# main.net
KiCad netlist of a schematic drawn in EAGLE
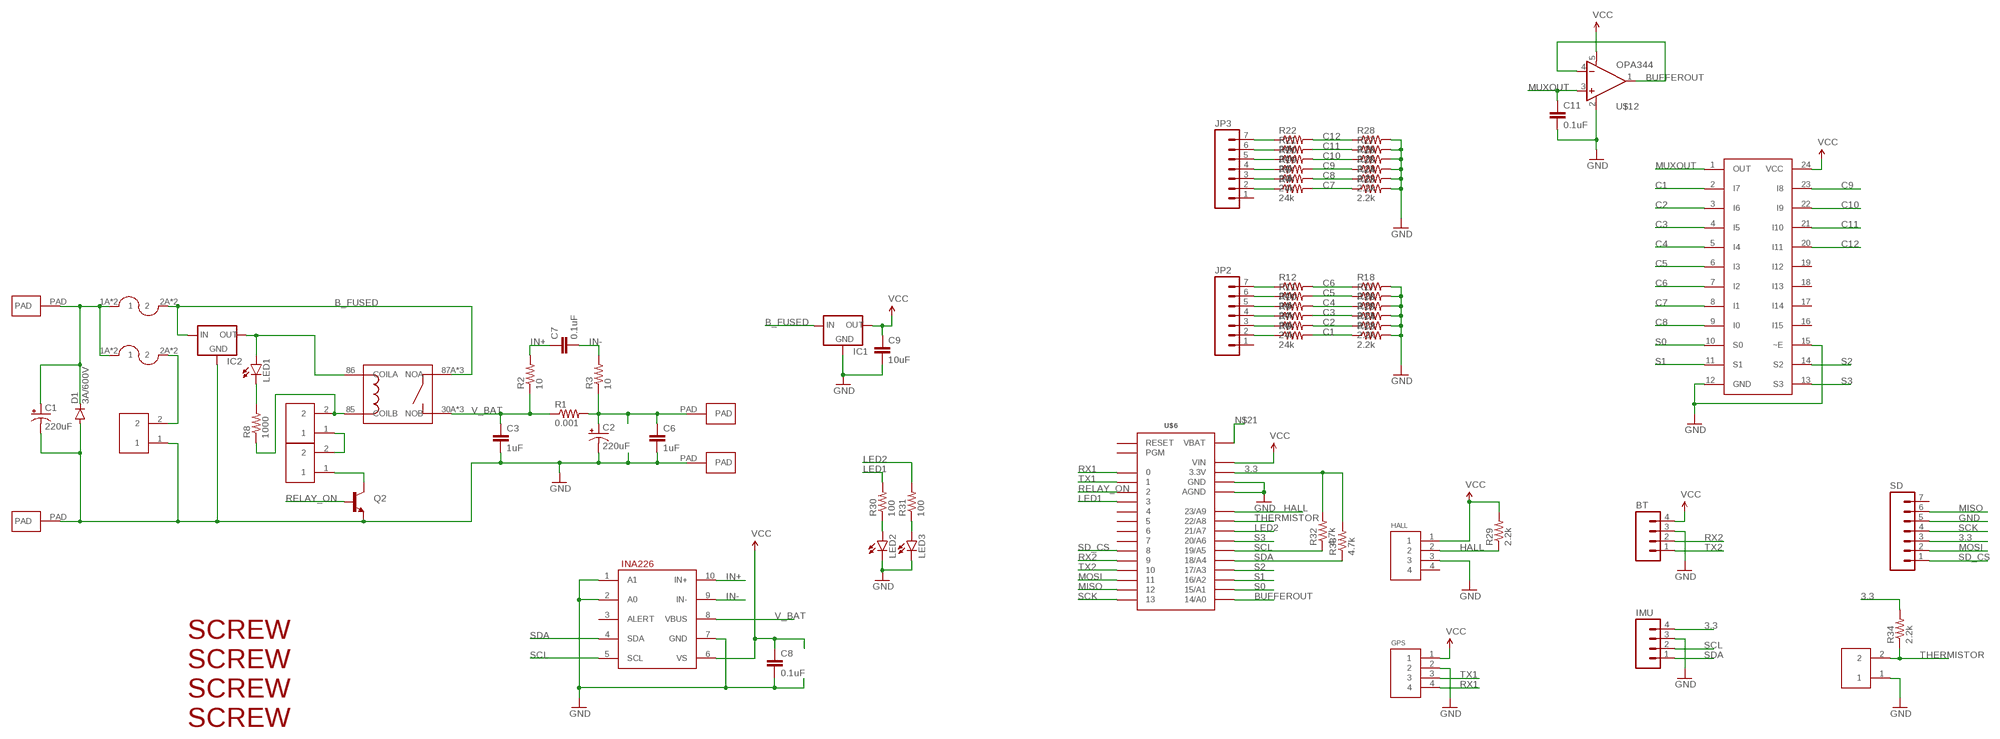
[diagram p0: schematic, sheet 1]

(export (version "E")
  (design (tool "Eeschema 10.0.6"))
  (components
    (comp (ref "BT")
      (value "M04PTH")
      (footprint "eagle-import:1X04")
      (libsource (lib "eagle-import") (part "M04PTH"))
    )
    (comp (ref "C1")
      (value "220uF")
      (footprint "eagle-import:CPOL-RADIAL-1000UF-25V")
      (libsource (lib "eagle-import") (part "CAP_POLPTH4"))
    )
    (comp (ref "C2")
      (value "220uF")
      (footprint "eagle-import:CPOL-RADIAL-1000UF-25V")
      (libsource (lib "eagle-import") (part "CAP_POLPTH4"))
    )
    (comp (ref "C3")
      (value "1uF")
      (footprint "eagle-import:1206")
      (libsource (lib "eagle-import") (part "CAP1206"))
    )
    (comp (ref "C6")
      (value "1uF")
      (footprint "eagle-import:1206")
      (libsource (lib "eagle-import") (part "CAP1206"))
    )
    (comp (ref "C7")
      (value "0.1uF")
      (footprint "eagle-import:0603-CAP")
      (libsource (lib "eagle-import") (part "SparkFun-Passives_CAP0603-CAP"))
    )
    (comp (ref "C8")
      (value "0.1uF")
      (footprint "eagle-import:0603-CAP")
      (libsource (lib "eagle-import") (part "SparkFun-Passives_CAP0603-CAP"))
    )
    (comp (ref "C9")
      (value "10uF")
      (footprint "eagle-import:0805")
      (libsource (lib "eagle-import") (part "SparkFun-Passives_CAP0805"))
    )
    (comp (ref "C11")
      (value "0.1uF")
      (footprint "eagle-import:0603-CAP")
      (libsource (lib "eagle-import") (part "SparkFun-Passives_CAP0603-CAP"))
    )
    (comp (ref "D1")
      (value "3A/600V")
      (footprint "eagle-import:SMC")
      (libsource (lib "eagle-import") (part "DIODEES3J"))
    )
    (comp (ref "GPS")
      (value "GPS")
      (footprint "eagle-import:4PINVALULOK")
      (libsource (lib "eagle-import") (part "HEADER4VALULOK"))
    )
    (comp (ref "HALL")
      (value "HEADER4VALULOK")
      (footprint "eagle-import:4PINVALULOK")
      (libsource (lib "eagle-import") (part "HEADER4VALULOK"))
    )
    (comp (ref "IC1")
      (value "V_REG_78XXSINK")
      (footprint "eagle-import:TO220-IGO")
      (libsource (lib "eagle-import") (part "V_REG_78XXSINK"))
    )
    (comp (ref "IC2")
      (value "V_REG_78XXSINK")
      (footprint "eagle-import:TO220-IGO")
      (libsource (lib "eagle-import") (part "V_REG_78XXSINK"))
    )
    (comp (ref "IMU")
      (value "M04PTH")
      (footprint "eagle-import:1X04")
      (libsource (lib "eagle-import") (part "M04PTH"))
    )
    (comp (ref "JP2")
      (value "M07")
      (footprint "eagle-import:1X07")
      (libsource (lib "eagle-import") (part "M07"))
    )
    (comp (ref "JP3")
      (value "M07")
      (footprint "eagle-import:1X07")
      (libsource (lib "eagle-import") (part "M07"))
    )
    (comp (ref "LED1")
      (value "LED1206")
      (footprint "eagle-import:LED-1206")
      (libsource (lib "eagle-import") (part "LED1206"))
    )
    (comp (ref "LED2")
      (value "LED1206")
      (footprint "eagle-import:LED-1206")
      (libsource (lib "eagle-import") (part "LED1206"))
    )
    (comp (ref "LED3")
      (value "LED1206")
      (footprint "eagle-import:LED-1206")
      (libsource (lib "eagle-import") (part "LED1206"))
    )
    (comp (ref "Q2")
      (value "TRANSISTOR_NPNSMD2")
      (footprint "eagle-import:SOT223")
      (libsource (lib "eagle-import") (part "TRANSISTOR_NPNSMD2"))
    )
    (comp (ref "R1")
      (value "0.001")
      (footprint "eagle-import:R2512")
      (libsource (lib "eagle-import") (part "SparkFun-Resistors_RESISTOR2512"))
    )
    (comp (ref "R2")
      (value "10")
      (footprint "eagle-import:0603-RES")
      (libsource (lib "eagle-import") (part "RESISTOR0603-RES"))
    )
    (comp (ref "R3")
      (value "10")
      (footprint "eagle-import:0603-RES")
      (libsource (lib "eagle-import") (part "RESISTOR0603-RES"))
    )
    (comp (ref "R4")
      (value "24k")
      (footprint "eagle-import:0603-RES")
      (libsource (lib "eagle-import") (part "RESISTOR0603-RES"))
    )
    (comp (ref "R5")
      (value "24k")
      (footprint "eagle-import:0603-RES")
      (libsource (lib "eagle-import") (part "RESISTOR0603-RES"))
    )
    (comp (ref "R6")
      (value "24k")
      (footprint "eagle-import:0603-RES")
      (libsource (lib "eagle-import") (part "RESISTOR0603-RES"))
    )
    (comp (ref "R7")
      (value "24k")
      (footprint "eagle-import:0603-RES")
      (libsource (lib "eagle-import") (part "RESISTOR0603-RES"))
    )
    (comp (ref "R8")
      (value "1000")
      (footprint "eagle-import:0603-RES")
      (libsource (lib "eagle-import") (part "RESISTOR0603-RES"))
    )
    (comp (ref "R9")
      (value "24k")
      (footprint "eagle-import:0603-RES")
      (libsource (lib "eagle-import") (part "RESISTOR0603-RES"))
    )
    (comp (ref "R10")
      (value "24k")
      (footprint "eagle-import:0603-RES")
      (libsource (lib "eagle-import") (part "RESISTOR0603-RES"))
    )
    (comp (ref "R11")
      (value "24k")
      (footprint "eagle-import:0603-RES")
      (libsource (lib "eagle-import") (part "RESISTOR0603-RES"))
    )
    (comp (ref "R12")
      (value "24k")
      (footprint "eagle-import:0603-RES")
      (libsource (lib "eagle-import") (part "RESISTOR0603-RES"))
    )
    (comp (ref "R13")
      (value "2.2k")
      (footprint "eagle-import:0603-RES")
      (libsource (lib "eagle-import") (part "RESISTOR0603-RES"))
    )
    (comp (ref "R14")
      (value "2.2k")
      (footprint "eagle-import:0603-RES")
      (libsource (lib "eagle-import") (part "RESISTOR0603-RES"))
    )
    (comp (ref "R15")
      (value "2.2k")
      (footprint "eagle-import:0603-RES")
      (libsource (lib "eagle-import") (part "RESISTOR0603-RES"))
    )
    (comp (ref "R16")
      (value "2.2k")
      (footprint "eagle-import:0603-RES")
      (libsource (lib "eagle-import") (part "RESISTOR0603-RES"))
    )
    (comp (ref "R17")
      (value "2.2k")
      (footprint "eagle-import:0603-RES")
      (libsource (lib "eagle-import") (part "RESISTOR0603-RES"))
    )
    (comp (ref "R18")
      (value "2.2k")
      (footprint "eagle-import:0603-RES")
      (libsource (lib "eagle-import") (part "RESISTOR0603-RES"))
    )
    (comp (ref "R19")
      (value "24k")
      (footprint "eagle-import:0603-RES")
      (libsource (lib "eagle-import") (part "RESISTOR0603-RES"))
    )
    (comp (ref "R20")
      (value "24k")
      (footprint "eagle-import:0603-RES")
      (libsource (lib "eagle-import") (part "RESISTOR0603-RES"))
    )
    (comp (ref "R21")
      (value "24k")
      (footprint "eagle-import:0603-RES")
      (libsource (lib "eagle-import") (part "RESISTOR0603-RES"))
    )
    (comp (ref "R22")
      (value "24k")
      (footprint "eagle-import:0603-RES")
      (libsource (lib "eagle-import") (part "RESISTOR0603-RES"))
    )
    (comp (ref "R23")
      (value "2.2k")
      (footprint "eagle-import:0603-RES")
      (libsource (lib "eagle-import") (part "RESISTOR0603-RES"))
    )
    (comp (ref "R24")
      (value "2.2k")
      (footprint "eagle-import:0603-RES")
      (libsource (lib "eagle-import") (part "RESISTOR0603-RES"))
    )
    (comp (ref "R25")
      (value "2.2k")
      (footprint "eagle-import:0603-RES")
      (libsource (lib "eagle-import") (part "RESISTOR0603-RES"))
    )
    (comp (ref "R26")
      (value "2.2k")
      (footprint "eagle-import:0603-RES")
      (libsource (lib "eagle-import") (part "RESISTOR0603-RES"))
    )
    (comp (ref "R27")
      (value "2.2k")
      (footprint "eagle-import:0603-RES")
      (libsource (lib "eagle-import") (part "RESISTOR0603-RES"))
    )
    (comp (ref "R28")
      (value "2.2k")
      (footprint "eagle-import:0603-RES")
      (libsource (lib "eagle-import") (part "RESISTOR0603-RES"))
    )
    (comp (ref "R29")
      (value "2.2k")
      (footprint "eagle-import:0603-RES")
      (libsource (lib "eagle-import") (part "RESISTOR0603-RES"))
    )
    (comp (ref "R30")
      (value "100")
      (footprint "eagle-import:0603-RES")
      (libsource (lib "eagle-import") (part "RESISTOR0603-RES"))
    )
    (comp (ref "R31")
      (value "100")
      (footprint "eagle-import:0603-RES")
      (libsource (lib "eagle-import") (part "RESISTOR0603-RES"))
    )
    (comp (ref "R32")
      (value "4.7k")
      (footprint "eagle-import:0603-RES")
      (libsource (lib "eagle-import") (part "RESISTOR0603-RES"))
    )
    (comp (ref "R33")
      (value "4.7k")
      (footprint "eagle-import:0603-RES")
      (libsource (lib "eagle-import") (part "RESISTOR0603-RES"))
    )
    (comp (ref "R34")
      (value "2.2k")
      (footprint "eagle-import:0603-RES")
      (libsource (lib "eagle-import") (part "RESISTOR0603-RES"))
    )
    (comp (ref "SD")
      (value "M07")
      (footprint "eagle-import:1X07")
      (libsource (lib "eagle-import") (part "M07"))
    )
    (comp (ref "U$1")
      (value "INA226")
      (footprint "eagle-import:PSOP-10")
      (libsource (lib "eagle-import") (part "INA226"))
    )
    (comp (ref "U$2")
      (value "PAD")
      (footprint "eagle-import:PAD")
      (libsource (lib "eagle-import") (part "PAD"))
    )
    (comp (ref "U$3")
      (value "PAD")
      (footprint "eagle-import:PAD")
      (libsource (lib "eagle-import") (part "PAD"))
    )
    (comp (ref "U$4")
      (value "PAD")
      (footprint "eagle-import:PAD")
      (libsource (lib "eagle-import") (part "PAD"))
    )
    (comp (ref "U$5")
      (value "PAD")
      (footprint "eagle-import:PAD")
      (libsource (lib "eagle-import") (part "PAD"))
    )
    (comp (ref "U$6")
      (value "TEENSY_3.0_BASIC")
      (footprint "eagle-import:TEENSY_3.0_BASIC")
      (libsource (lib "eagle-import") (part "TEENSY_3.0_BASIC"))
    )
    (comp (ref "U$7")
      (value "RELAY")
      (footprint "eagle-import:PANASONIC_HP_RELAY")
      (libsource (lib "eagle-import") (part "RELAY"))
    )
    (comp (ref "U$8")
      (value "FUSE")
      (footprint "eagle-import:AUTO_FUSE")
      (libsource (lib "eagle-import") (part "FUSE"))
    )
    (comp (ref "U$9")
      (value "HEADER2")
      (footprint "eagle-import:2PINVALULOK")
      (libsource (lib "eagle-import") (part "HEADER2"))
    )
    (comp (ref "U$10")
      (value "HEADER2")
      (footprint "eagle-import:2PINVALULOK")
      (libsource (lib "eagle-import") (part "HEADER2"))
    )
    (comp (ref "U$11")
      (value "CD74HC4067")
      (footprint "eagle-import:SO-24DW")
      (libsource (lib "eagle-import") (part "CD74HC4067"))
    )
    (comp (ref "U$12")
      (value "OPA344")
      (footprint "eagle-import:SOT23-5")
      (libsource (lib "eagle-import") (part "OPA344"))
    )
    (comp (ref "U$13")
      (value "SCREW")
      (footprint "eagle-import:M3HOLE")
      (libsource (lib "eagle-import") (part "SCREW"))
    )
    (comp (ref "U$14")
      (value "SCREW")
      (footprint "eagle-import:M3HOLE")
      (libsource (lib "eagle-import") (part "SCREW"))
    )
    (comp (ref "U$15")
      (value "SCREW")
      (footprint "eagle-import:M3HOLE")
      (libsource (lib "eagle-import") (part "SCREW"))
    )
    (comp (ref "U$16")
      (value "SCREW")
      (footprint "eagle-import:M3HOLE")
      (libsource (lib "eagle-import") (part "SCREW"))
    )
    (comp (ref "U$17")
      (value "HEADER2")
      (footprint "eagle-import:2PINVALULOK")
      (libsource (lib "eagle-import") (part "HEADER2"))
    )
    (comp (ref "U$18")
      (value "FUSE")
      (footprint "eagle-import:AUTO_FUSE")
      (libsource (lib "eagle-import") (part "FUSE"))
    )
    (comp (ref "U$19")
      (value "HEADER2")
      (footprint "eagle-import:2PINVALULOK")
      (libsource (lib "eagle-import") (part "HEADER2"))
    )
  )
  (nets
    (net (code "1") (name "/3.3") (class "Default")
      (node (ref "IMU") (pin "4") (pinfunction "4_4") (pintype "passive"))
      (node (ref "R32") (pin "2") (pinfunction "2_2") (pintype "passive"))
      (node (ref "R33") (pin "2") (pinfunction "2_2") (pintype "passive"))
      (node (ref "R34") (pin "2") (pinfunction "2_2") (pintype "passive"))
      (node (ref "SD") (pin "3") (pinfunction "3_3") (pintype "passive"))
      (node (ref "U$6") (pin "3.3V") (pinfunction "3.3V_3.3V") (pintype "power_in"))
      (node (ref "U$6") (pin "3.3V1") (pinfunction "3.3V_3.3V1") (pintype "power_in"))
    )
    (net (code "2") (name "/BUFFEROUT") (class "Default")
      (node (ref "U$12") (pin "1") (pinfunction "OUT_1") (pintype "output"))
      (node (ref "U$12") (pin "4") (pinfunction "-IN_4") (pintype "input"))
      (node (ref "U$6") (pin "14/A0") (pinfunction "14/A0_14/A0") (pintype "bidirectional"))
    )
    (net (code "3") (name "/B_FUSED") (class "Default")
      (node (ref "IC1") (pin "IN") (pinfunction "IN_IN") (pintype "input"))
      (node (ref "IC2") (pin "IN") (pinfunction "IN_IN") (pintype "input"))
      (node (ref "U$7") (pin "87A") (pinfunction "NOA_87A") (pintype "bidirectional"))
      (node (ref "U$7") (pin "87B") (pinfunction "NOA_87B") (pintype "bidirectional"))
      (node (ref "U$7") (pin "87C") (pinfunction "NOA_87C") (pintype "bidirectional"))
      (node (ref "U$8") (pin "2A") (pinfunction "2_2A") (pintype "bidirectional"))
      (node (ref "U$8") (pin "2B") (pinfunction "2_2B") (pintype "bidirectional"))
    )
    (net (code "4") (name "/C1") (class "Default")
      (node (ref "R13") (pin "1") (pinfunction "1_1") (pintype "passive"))
      (node (ref "R6") (pin "2") (pinfunction "2_2") (pintype "passive"))
      (node (ref "U$11") (pin "2") (pinfunction "I7_2") (pintype "bidirectional"))
    )
    (net (code "5") (name "/C2") (class "Default")
      (node (ref "R14") (pin "1") (pinfunction "1_1") (pintype "passive"))
      (node (ref "R7") (pin "2") (pinfunction "2_2") (pintype "passive"))
      (node (ref "U$11") (pin "3") (pinfunction "I6_3") (pintype "bidirectional"))
    )
    (net (code "6") (name "/C3") (class "Default")
      (node (ref "R15") (pin "1") (pinfunction "1_1") (pintype "passive"))
      (node (ref "R9") (pin "2") (pinfunction "2_2") (pintype "passive"))
      (node (ref "U$11") (pin "4") (pinfunction "I5_4") (pintype "bidirectional"))
    )
    (net (code "7") (name "/C4") (class "Default")
      (node (ref "R10") (pin "2") (pinfunction "2_2") (pintype "passive"))
      (node (ref "R16") (pin "1") (pinfunction "1_1") (pintype "passive"))
      (node (ref "U$11") (pin "5") (pinfunction "I4_5") (pintype "bidirectional"))
    )
    (net (code "8") (name "/C5") (class "Default")
      (node (ref "R11") (pin "2") (pinfunction "2_2") (pintype "passive"))
      (node (ref "R17") (pin "1") (pinfunction "1_1") (pintype "passive"))
      (node (ref "U$11") (pin "6") (pinfunction "I3_6") (pintype "bidirectional"))
    )
    (net (code "9") (name "/C6") (class "Default")
      (node (ref "R12") (pin "2") (pinfunction "2_2") (pintype "passive"))
      (node (ref "R18") (pin "1") (pinfunction "1_1") (pintype "passive"))
      (node (ref "U$11") (pin "7") (pinfunction "I2_7") (pintype "bidirectional"))
    )
    (net (code "10") (name "/C7") (class "Default")
      (node (ref "R23") (pin "1") (pinfunction "1_1") (pintype "passive"))
      (node (ref "R4") (pin "2") (pinfunction "2_2") (pintype "passive"))
      (node (ref "U$11") (pin "8") (pinfunction "I1_8") (pintype "bidirectional"))
    )
    (net (code "11") (name "/C8") (class "Default")
      (node (ref "R24") (pin "1") (pinfunction "1_1") (pintype "passive"))
      (node (ref "R5") (pin "2") (pinfunction "2_2") (pintype "passive"))
      (node (ref "U$11") (pin "9") (pinfunction "I0_9") (pintype "bidirectional"))
    )
    (net (code "12") (name "/C9") (class "Default")
      (node (ref "R19") (pin "2") (pinfunction "2_2") (pintype "passive"))
      (node (ref "R25") (pin "1") (pinfunction "1_1") (pintype "passive"))
      (node (ref "U$11") (pin "23") (pinfunction "I8_23") (pintype "bidirectional"))
    )
    (net (code "13") (name "/C10") (class "Default")
      (node (ref "R20") (pin "2") (pinfunction "2_2") (pintype "passive"))
      (node (ref "R26") (pin "1") (pinfunction "1_1") (pintype "passive"))
      (node (ref "U$11") (pin "22") (pinfunction "I9_22") (pintype "bidirectional"))
    )
    (net (code "14") (name "/C11") (class "Default")
      (node (ref "R21") (pin "2") (pinfunction "2_2") (pintype "passive"))
      (node (ref "R27") (pin "1") (pinfunction "1_1") (pintype "passive"))
      (node (ref "U$11") (pin "21") (pinfunction "I10_21") (pintype "bidirectional"))
    )
    (net (code "15") (name "/C12") (class "Default")
      (node (ref "R22") (pin "2") (pinfunction "2_2") (pintype "passive"))
      (node (ref "R28") (pin "1") (pinfunction "1_1") (pintype "passive"))
      (node (ref "U$11") (pin "20") (pinfunction "I11_20") (pintype "bidirectional"))
    )
    (net (code "16") (name "/HALL") (class "Default")
      (node (ref "HALL") (pin "2") (pinfunction "2_2") (pintype "bidirectional"))
      (node (ref "R29") (pin "1") (pinfunction "1_1") (pintype "passive"))
      (node (ref "U$6") (pin "23/A9") (pinfunction "23/A9_23/A9") (pintype "bidirectional"))
    )
    (net (code "17") (name "/IN+") (class "Default")
      (node (ref "C7") (pin "1") (pinfunction "1_1") (pintype "passive"))
      (node (ref "R2") (pin "2") (pinfunction "2_2") (pintype "passive"))
      (node (ref "U$1") (pin "10") (pinfunction "IN+_10") (pintype "bidirectional"))
    )
    (net (code "18") (name "/IN-") (class "Default")
      (node (ref "C7") (pin "2") (pinfunction "2_2") (pintype "passive"))
      (node (ref "R3") (pin "2") (pinfunction "2_2") (pintype "passive"))
      (node (ref "U$1") (pin "9") (pinfunction "IN-_9") (pintype "bidirectional"))
    )
    (net (code "19") (name "/LED1") (class "Default")
      (node (ref "R30") (pin "2") (pinfunction "2_2") (pintype "passive"))
      (node (ref "U$6") (pin "3") (pinfunction "3_3") (pintype "bidirectional"))
    )
    (net (code "20") (name "/LED2") (class "Default")
      (node (ref "R31") (pin "2") (pinfunction "2_2") (pintype "passive"))
      (node (ref "U$6") (pin "21/A7") (pinfunction "21/A7_21/A7") (pintype "bidirectional"))
    )
    (net (code "21") (name "/MISO") (class "Default")
      (node (ref "SD") (pin "6") (pinfunction "6_6") (pintype "passive"))
      (node (ref "U$6") (pin "12") (pinfunction "12_12") (pintype "bidirectional"))
    )
    (net (code "22") (name "/MOSI") (class "Default")
      (node (ref "SD") (pin "2") (pinfunction "2_2") (pintype "passive"))
      (node (ref "U$6") (pin "11") (pinfunction "11_11") (pintype "bidirectional"))
    )
    (net (code "23") (name "/MUXOUT") (class "Default")
      (node (ref "C11") (pin "1") (pinfunction "1_1") (pintype "passive"))
      (node (ref "U$11") (pin "1") (pinfunction "OUT_1") (pintype "bidirectional"))
      (node (ref "U$12") (pin "3") (pinfunction "+IN_3") (pintype "input"))
    )
    (net (code "24") (name "/N$21") (class "Default")
      (node (ref "U$6") (pin "VBAT") (pinfunction "VBAT_VBAT") (pintype "power_in"))
    )
    (net (code "25") (name "/RELAY_ON") (class "Default")
      (node (ref "Q2") (pin "1") (pinfunction "B_1") (pintype "passive"))
      (node (ref "U$6") (pin "2") (pinfunction "2_2") (pintype "bidirectional"))
    )
    (net (code "26") (name "/RX1") (class "Default")
      (node (ref "GPS") (pin "4") (pinfunction "4_4") (pintype "bidirectional"))
      (node (ref "U$6") (pin "0") (pinfunction "0_0") (pintype "bidirectional"))
    )
    (net (code "27") (name "/RX2") (class "Default")
      (node (ref "BT") (pin "2") (pinfunction "2_2") (pintype "passive"))
      (node (ref "U$6") (pin "9") (pinfunction "9_9") (pintype "bidirectional"))
    )
    (net (code "28") (name "/S0") (class "Default")
      (node (ref "U$11") (pin "10") (pinfunction "S0_10") (pintype "bidirectional"))
      (node (ref "U$6") (pin "15/A1") (pinfunction "15/A1_15/A1") (pintype "bidirectional"))
    )
    (net (code "29") (name "/S1") (class "Default")
      (node (ref "U$11") (pin "11") (pinfunction "S1_11") (pintype "bidirectional"))
      (node (ref "U$6") (pin "16/A2") (pinfunction "16/A2_16/A2") (pintype "bidirectional"))
    )
    (net (code "30") (name "/S2") (class "Default")
      (node (ref "U$11") (pin "14") (pinfunction "S2_14") (pintype "bidirectional"))
      (node (ref "U$6") (pin "17/A3") (pinfunction "17/A3_17/A3") (pintype "bidirectional"))
    )
    (net (code "31") (name "/S3") (class "Default")
      (node (ref "U$11") (pin "13") (pinfunction "S3_13") (pintype "bidirectional"))
      (node (ref "U$6") (pin "20/A6") (pinfunction "20/A6_20/A6") (pintype "bidirectional"))
    )
    (net (code "32") (name "/SCK") (class "Default")
      (node (ref "SD") (pin "4") (pinfunction "4_4") (pintype "passive"))
      (node (ref "U$6") (pin "13") (pinfunction "13_13") (pintype "bidirectional"))
    )
    (net (code "33") (name "/SCL") (class "Default")
      (node (ref "IMU") (pin "2") (pinfunction "2_2") (pintype "passive"))
      (node (ref "R32") (pin "1") (pinfunction "1_1") (pintype "passive"))
      (node (ref "U$1") (pin "5") (pinfunction "SCL_5") (pintype "bidirectional"))
      (node (ref "U$6") (pin "19/A5") (pinfunction "19/A5_19/A5") (pintype "bidirectional"))
    )
    (net (code "34") (name "/SDA") (class "Default")
      (node (ref "IMU") (pin "1") (pinfunction "1_1") (pintype "passive"))
      (node (ref "R33") (pin "1") (pinfunction "1_1") (pintype "passive"))
      (node (ref "U$1") (pin "4") (pinfunction "SDA_4") (pintype "bidirectional"))
      (node (ref "U$6") (pin "18/A4") (pinfunction "18/A4_18/A4") (pintype "bidirectional"))
    )
    (net (code "35") (name "/SD_CS") (class "Default")
      (node (ref "SD") (pin "1") (pinfunction "1_1") (pintype "passive"))
      (node (ref "U$6") (pin "8") (pinfunction "8_8") (pintype "bidirectional"))
    )
    (net (code "36") (name "/THERMISTOR") (class "Default")
      (node (ref "R34") (pin "1") (pinfunction "1_1") (pintype "passive"))
      (node (ref "U$17") (pin "2") (pinfunction "2_2") (pintype "bidirectional"))
      (node (ref "U$6") (pin "22/A8") (pinfunction "22/A8_22/A8") (pintype "bidirectional"))
    )
    (net (code "37") (name "/TX1") (class "Default")
      (node (ref "GPS") (pin "3") (pinfunction "3_3") (pintype "bidirectional"))
      (node (ref "U$6") (pin "1") (pinfunction "1_1") (pintype "bidirectional"))
    )
    (net (code "38") (name "/TX2") (class "Default")
      (node (ref "BT") (pin "1") (pinfunction "1_1") (pintype "passive"))
      (node (ref "U$6") (pin "10") (pinfunction "10_10") (pintype "bidirectional"))
    )
    (net (code "39") (name "/V_BAT") (class "Default")
      (node (ref "C3") (pin "1") (pinfunction "1_1") (pintype "passive"))
      (node (ref "R1") (pin "1") (pinfunction "1_1") (pintype "passive"))
      (node (ref "R2") (pin "1") (pinfunction "1_1") (pintype "passive"))
      (node (ref "U$1") (pin "8") (pinfunction "VBUS_8") (pintype "bidirectional"))
      (node (ref "U$7") (pin "30A") (pinfunction "NOB_30A") (pintype "bidirectional"))
      (node (ref "U$7") (pin "30B") (pinfunction "NOB_30B") (pintype "bidirectional"))
      (node (ref "U$7") (pin "30C") (pinfunction "NOB_30C") (pintype "bidirectional"))
    )
    (net (code "40") (name "GND") (class "Default")
      (node (ref "BT") (pin "3") (pinfunction "3_3") (pintype "passive"))
      (node (ref "C1") (pin "-") (pinfunction "-_-") (pintype "passive"))
      (node (ref "C11") (pin "2") (pinfunction "2_2") (pintype "passive"))
      (node (ref "C2") (pin "-") (pinfunction "-_-") (pintype "passive"))
      (node (ref "C3") (pin "2") (pinfunction "2_2") (pintype "passive"))
      (node (ref "C6") (pin "2") (pinfunction "2_2") (pintype "passive"))
      (node (ref "C8") (pin "2") (pinfunction "2_2") (pintype "passive"))
      (node (ref "C9") (pin "2") (pinfunction "2_2") (pintype "passive"))
      (node (ref "D1") (pin "A") (pinfunction "A_A") (pintype "passive"))
      (node (ref "GPS") (pin "2") (pinfunction "2_2") (pintype "bidirectional"))
      (node (ref "HALL") (pin "3") (pinfunction "3_3") (pintype "bidirectional"))
      (node (ref "IC1") (pin "GND") (pinfunction "GND_GND") (pintype "input"))
      (node (ref "IC2") (pin "GND") (pinfunction "GND_GND") (pintype "input"))
      (node (ref "IMU") (pin "3") (pinfunction "3_3") (pintype "passive"))
      (node (ref "LED2") (pin "C") (pinfunction "C_C") (pintype "passive"))
      (node (ref "LED3") (pin "C") (pinfunction "C_C") (pintype "passive"))
      (node (ref "Q2") (pin "3") (pinfunction "E_3") (pintype "passive"))
      (node (ref "R13") (pin "2") (pinfunction "2_2") (pintype "passive"))
      (node (ref "R14") (pin "2") (pinfunction "2_2") (pintype "passive"))
      (node (ref "R15") (pin "2") (pinfunction "2_2") (pintype "passive"))
      (node (ref "R16") (pin "2") (pinfunction "2_2") (pintype "passive"))
      (node (ref "R17") (pin "2") (pinfunction "2_2") (pintype "passive"))
      (node (ref "R18") (pin "2") (pinfunction "2_2") (pintype "passive"))
      (node (ref "R23") (pin "2") (pinfunction "2_2") (pintype "passive"))
      (node (ref "R24") (pin "2") (pinfunction "2_2") (pintype "passive"))
      (node (ref "R25") (pin "2") (pinfunction "2_2") (pintype "passive"))
      (node (ref "R26") (pin "2") (pinfunction "2_2") (pintype "passive"))
      (node (ref "R27") (pin "2") (pinfunction "2_2") (pintype "passive"))
      (node (ref "R28") (pin "2") (pinfunction "2_2") (pintype "passive"))
      (node (ref "SD") (pin "5") (pinfunction "5_5") (pintype "passive"))
      (node (ref "U$1") (pin "1") (pinfunction "A1_1") (pintype "bidirectional"))
      (node (ref "U$1") (pin "2") (pinfunction "A0_2") (pintype "bidirectional"))
      (node (ref "U$1") (pin "7") (pinfunction "GND_7") (pintype "bidirectional"))
      (node (ref "U$11") (pin "12") (pinfunction "GND_12") (pintype "bidirectional"))
      (node (ref "U$11") (pin "15") (pinfunction "~{E}_15") (pintype "bidirectional"))
      (node (ref "U$12") (pin "2") (pinfunction "V-_2") (pintype "power_in"))
      (node (ref "U$17") (pin "1") (pinfunction "1_1") (pintype "bidirectional"))
      (node (ref "U$19") (pin "1") (pinfunction "1_1") (pintype "bidirectional"))
      (node (ref "U$3") (pin "PAD") (pinfunction "PAD_PAD") (pintype "bidirectional"))
      (node (ref "U$5") (pin "PAD") (pinfunction "PAD_PAD") (pintype "bidirectional"))
      (node (ref "U$6") (pin "AGND") (pinfunction "AGND_AGND") (pintype "power_in"))
      (node (ref "U$6") (pin "GND") (pinfunction "GND_GND") (pintype "power_in"))
      (node (ref "U$6") (pin "GND1") (pinfunction "GND_GND1") (pintype "power_in"))
    )
    (net (code "41") (name "Net-(C1-Pad+)") (class "Default")
      (node (ref "C1") (pin "+") (pinfunction "+_+") (pintype "passive"))
      (node (ref "D1") (pin "C") (pinfunction "C_C") (pintype "passive"))
      (node (ref "U$18") (pin "1A") (pinfunction "1_1A") (pintype "bidirectional"))
      (node (ref "U$18") (pin "1B") (pinfunction "1_1B") (pintype "bidirectional"))
      (node (ref "U$2") (pin "PAD") (pinfunction "PAD_PAD") (pintype "bidirectional"))
      (node (ref "U$8") (pin "1A") (pinfunction "1_1A") (pintype "bidirectional"))
      (node (ref "U$8") (pin "1B") (pinfunction "1_1B") (pintype "bidirectional"))
    )
    (net (code "42") (name "Net-(C2-Pad+)") (class "Default")
      (node (ref "C2") (pin "+") (pinfunction "+_+") (pintype "passive"))
      (node (ref "C6") (pin "1") (pinfunction "1_1") (pintype "passive"))
      (node (ref "R1") (pin "2") (pinfunction "2_2") (pintype "passive"))
      (node (ref "R3") (pin "1") (pinfunction "1_1") (pintype "passive"))
      (node (ref "U$4") (pin "PAD") (pinfunction "PAD_PAD") (pintype "bidirectional"))
    )
    (net (code "43") (name "Net-(JP2-Pad2)") (class "Default")
      (node (ref "JP2") (pin "2") (pinfunction "2_2") (pintype "passive"))
      (node (ref "R6") (pin "1") (pinfunction "1_1") (pintype "passive"))
    )
    (net (code "44") (name "Net-(JP2-Pad3)") (class "Default")
      (node (ref "JP2") (pin "3") (pinfunction "3_3") (pintype "passive"))
      (node (ref "R7") (pin "1") (pinfunction "1_1") (pintype "passive"))
    )
    (net (code "45") (name "Net-(JP2-Pad4)") (class "Default")
      (node (ref "JP2") (pin "4") (pinfunction "4_4") (pintype "passive"))
      (node (ref "R9") (pin "1") (pinfunction "1_1") (pintype "passive"))
    )
    (net (code "46") (name "Net-(JP2-Pad5)") (class "Default")
      (node (ref "JP2") (pin "5") (pinfunction "5_5") (pintype "passive"))
      (node (ref "R10") (pin "1") (pinfunction "1_1") (pintype "passive"))
    )
    (net (code "47") (name "Net-(JP2-Pad6)") (class "Default")
      (node (ref "JP2") (pin "6") (pinfunction "6_6") (pintype "passive"))
      (node (ref "R11") (pin "1") (pinfunction "1_1") (pintype "passive"))
    )
    (net (code "48") (name "Net-(JP2-Pad7)") (class "Default")
      (node (ref "JP2") (pin "7") (pinfunction "7_7") (pintype "passive"))
      (node (ref "R12") (pin "1") (pinfunction "1_1") (pintype "passive"))
    )
    (net (code "49") (name "Net-(JP3-Pad2)") (class "Default")
      (node (ref "JP3") (pin "2") (pinfunction "2_2") (pintype "passive"))
      (node (ref "R4") (pin "1") (pinfunction "1_1") (pintype "passive"))
    )
    (net (code "50") (name "Net-(JP3-Pad3)") (class "Default")
      (node (ref "JP3") (pin "3") (pinfunction "3_3") (pintype "passive"))
      (node (ref "R5") (pin "1") (pinfunction "1_1") (pintype "passive"))
    )
    (net (code "51") (name "Net-(JP3-Pad4)") (class "Default")
      (node (ref "JP3") (pin "4") (pinfunction "4_4") (pintype "passive"))
      (node (ref "R19") (pin "1") (pinfunction "1_1") (pintype "passive"))
    )
    (net (code "52") (name "Net-(JP3-Pad5)") (class "Default")
      (node (ref "JP3") (pin "5") (pinfunction "5_5") (pintype "passive"))
      (node (ref "R20") (pin "1") (pinfunction "1_1") (pintype "passive"))
    )
    (net (code "53") (name "Net-(JP3-Pad6)") (class "Default")
      (node (ref "JP3") (pin "6") (pinfunction "6_6") (pintype "passive"))
      (node (ref "R21") (pin "1") (pinfunction "1_1") (pintype "passive"))
    )
    (net (code "54") (name "Net-(JP3-Pad7)") (class "Default")
      (node (ref "JP3") (pin "7") (pinfunction "7_7") (pintype "passive"))
      (node (ref "R22") (pin "1") (pinfunction "1_1") (pintype "passive"))
    )
    (net (code "55") (name "Net-(LED1-PadC)") (class "Default")
      (node (ref "LED1") (pin "C") (pinfunction "C_C") (pintype "passive"))
      (node (ref "R8") (pin "2") (pinfunction "2_2") (pintype "passive"))
    )
    (net (code "56") (name "Net-(LED2-PadA)") (class "Default")
      (node (ref "LED2") (pin "A") (pinfunction "A_A") (pintype "passive"))
      (node (ref "R30") (pin "1") (pinfunction "1_1") (pintype "passive"))
    )
    (net (code "57") (name "Net-(LED3-PadA)") (class "Default")
      (node (ref "LED3") (pin "A") (pinfunction "A_A") (pintype "passive"))
      (node (ref "R31") (pin "1") (pinfunction "1_1") (pintype "passive"))
    )
    (net (code "58") (name "Net-(Q2-C)") (class "Default")
      (node (ref "Q2") (pin "2") (pinfunction "C_2") (pintype "passive"))
      (node (ref "U$10") (pin "1") (pinfunction "1_1") (pintype "bidirectional"))
    )
    (net (code "59") (name "Net-(U$7-COILA)") (class "Default")
      (node (ref "IC2") (pin "OUT") (pinfunction "OUT_OUT") (pintype "output"))
      (node (ref "LED1") (pin "A") (pinfunction "A_A") (pintype "passive"))
      (node (ref "U$7") (pin "86") (pinfunction "COILA_86") (pintype "bidirectional"))
    )
    (net (code "60") (name "Net-(U$7-COILB)") (class "Default")
      (node (ref "R8") (pin "1") (pinfunction "1_1") (pintype "passive"))
      (node (ref "U$7") (pin "85") (pinfunction "COILB_85") (pintype "bidirectional"))
      (node (ref "U$9") (pin "2") (pinfunction "2_2") (pintype "bidirectional"))
    )
    (net (code "61") (name "Net-(U$10-Pad2)") (class "Default")
      (node (ref "U$10") (pin "2") (pinfunction "2_2") (pintype "bidirectional"))
      (node (ref "U$9") (pin "1") (pinfunction "1_1") (pintype "bidirectional"))
    )
    (net (code "62") (name "Net-(U$18-2-Pad2A)") (class "Default")
      (node (ref "U$18") (pin "2A") (pinfunction "2_2A") (pintype "bidirectional"))
      (node (ref "U$18") (pin "2B") (pinfunction "2_2B") (pintype "bidirectional"))
      (node (ref "U$19") (pin "2") (pinfunction "2_2") (pintype "bidirectional"))
    )
    (net (code "63") (name "VCC") (class "Default")
      (node (ref "BT") (pin "4") (pinfunction "4_4") (pintype "passive"))
      (node (ref "C8") (pin "1") (pinfunction "1_1") (pintype "passive"))
      (node (ref "C9") (pin "1") (pinfunction "1_1") (pintype "passive"))
      (node (ref "GPS") (pin "1") (pinfunction "1_1") (pintype "bidirectional"))
      (node (ref "HALL") (pin "1") (pinfunction "1_1") (pintype "bidirectional"))
      (node (ref "IC1") (pin "OUT") (pinfunction "OUT_OUT") (pintype "output"))
      (node (ref "R29") (pin "2") (pinfunction "2_2") (pintype "passive"))
      (node (ref "U$1") (pin "6") (pinfunction "VS_6") (pintype "bidirectional"))
      (node (ref "U$11") (pin "24") (pinfunction "VCC_24") (pintype "bidirectional"))
      (node (ref "U$12") (pin "5") (pinfunction "V+_5") (pintype "power_in"))
      (node (ref "U$6") (pin "VIN") (pinfunction "VIN_VIN") (pintype "power_in"))
    )
    (net (code "64") (name "unconnected-(HALL-Pad4)") (class "Default")
      (node (ref "HALL") (pin "4") (pinfunction "4_4") (pintype "bidirectional"))
    )
    (net (code "65") (name "unconnected-(JP2-Pad1)") (class "Default")
      (node (ref "JP2") (pin "1") (pinfunction "1_1") (pintype "passive"))
    )
    (net (code "66") (name "unconnected-(JP3-Pad1)") (class "Default")
      (node (ref "JP3") (pin "1") (pinfunction "1_1") (pintype "passive"))
    )
    (net (code "67") (name "unconnected-(SD-Pad7)") (class "Default")
      (node (ref "SD") (pin "7") (pinfunction "7_7") (pintype "passive"))
    )
    (net (code "68") (name "unconnected-(U$1-ALERT-Pad3)") (class "Default")
      (node (ref "U$1") (pin "3") (pinfunction "ALERT_3") (pintype "bidirectional"))
    )
    (net (code "69") (name "unconnected-(U$6-Pad4)") (class "Default")
      (node (ref "U$6") (pin "4") (pinfunction "4_4") (pintype "bidirectional"))
    )
    (net (code "70") (name "unconnected-(U$6-Pad5)") (class "Default")
      (node (ref "U$6") (pin "5") (pinfunction "5_5") (pintype "bidirectional"))
    )
    (net (code "71") (name "unconnected-(U$6-Pad6)") (class "Default")
      (node (ref "U$6") (pin "6") (pinfunction "6_6") (pintype "bidirectional"))
    )
    (net (code "72") (name "unconnected-(U$6-Pad7)") (class "Default")
      (node (ref "U$6") (pin "7") (pinfunction "7_7") (pintype "bidirectional"))
    )
    (net (code "73") (name "unconnected-(U$6-PadPGM)") (class "Default")
      (node (ref "U$6") (pin "PGM") (pinfunction "PGM_PGM") (pintype "bidirectional"))
    )
    (net (code "74") (name "unconnected-(U$6-PadRESET)") (class "Default")
      (node (ref "U$6") (pin "RESET") (pinfunction "RESET_RESET") (pintype "bidirectional"))
    )
    (net (code "75") (name "unconnected-(U$11-I12-Pad19)") (class "Default")
      (node (ref "U$11") (pin "19") (pinfunction "I12_19") (pintype "bidirectional"))
    )
    (net (code "76") (name "unconnected-(U$11-I13-Pad18)") (class "Default")
      (node (ref "U$11") (pin "18") (pinfunction "I13_18") (pintype "bidirectional"))
    )
    (net (code "77") (name "unconnected-(U$11-I14-Pad17)") (class "Default")
      (node (ref "U$11") (pin "17") (pinfunction "I14_17") (pintype "bidirectional"))
    )
    (net (code "78") (name "unconnected-(U$11-I15-Pad16)") (class "Default")
      (node (ref "U$11") (pin "16") (pinfunction "I15_16") (pintype "bidirectional"))
    )
  )
)
